# main.net
KiCad netlist of a schematic drawn in Altium Designer
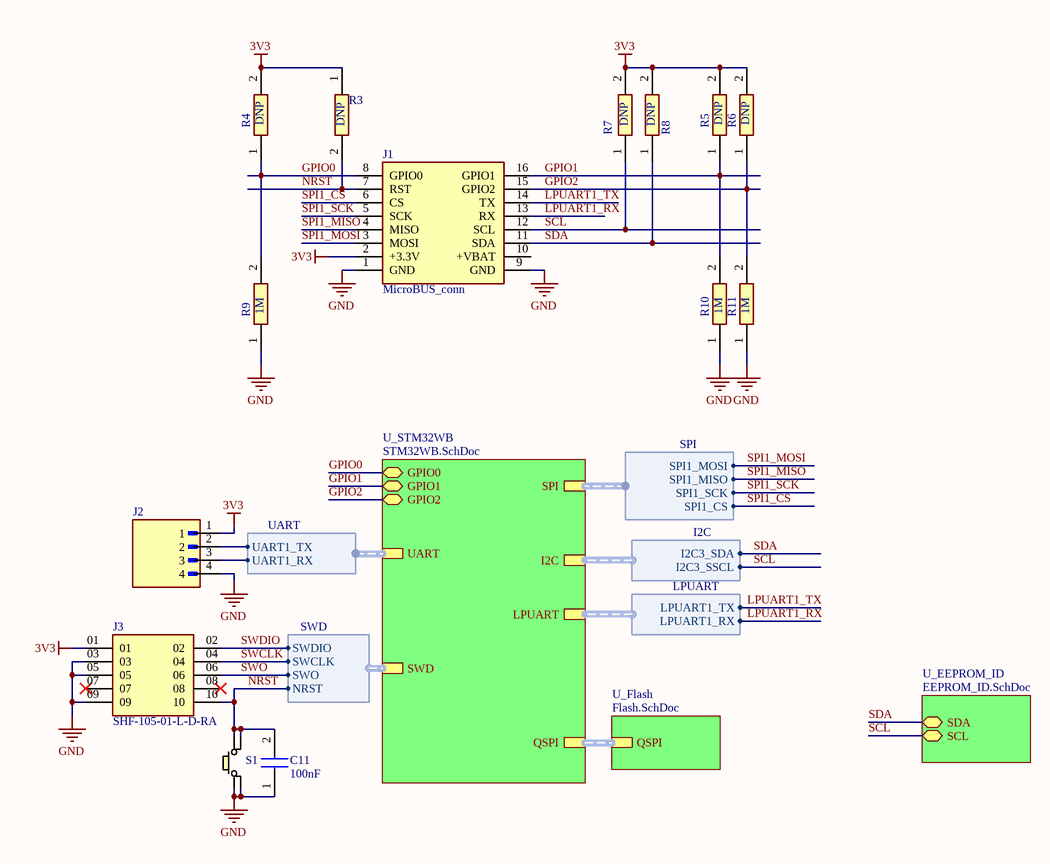
[diagram p0: main.SchDoc]

(export (version "E")
  (design (tool "Eeschema 10.0.6"))
  (components
    (comp (ref "C11")
      (value "100nF")
      (footprint "SamacSys:CAPC1005X70N")
      (description "Capacitor")
      (fields
        (field (name "MANUFACTURER_PART_NUMBER") "GRM155R61A104KA01D")
        (field (name "MOUSER PART NUMBER") "81-GRM155R61A104KA01")
      )
      (libsource (lib "*") (part "GRM155R61A104KA01D"))
    )
    (comp (ref "J1")
      (value "MicroBUS_conn")
      (footprint "SamacSys:MicroBUS_header")
      (description "Connector")
      (fields
        (field (name "MANUFACTURER_PART_NUMBER") "M20-9730845")
        (field (name "MOUSER PART NUMBER") "855-M20-9730845")
      )
      (libsource (lib "SamacSys") (part "MicroBUS_conn"))
    )
    (comp (ref "J2")
      (value "310-87-104-41-205101")
      (footprint "SamacSys:310-87-104-41-205101")
      (libsource (lib "SamacSys") (part "310-87-104-41-205101"))
    )
    (comp (ref "J3")
      (value "SHF-105-01-L-D-RA")
      (footprint "SamacSys:SAMTEC_SHF-105-01-L-D-RA")
      (fields (field (name "MF") "Samtec"))
      (libsource (lib "SamacSys") (part "SHF-105-01-L-D-RA"))
    )
    (comp (ref "R3")
      (value "DNP")
      (footprint "SamacSys:RESC1005X35N")
      (description "Resistor")
      (fields
        (field (name "MANUFACTURER_PART_NUMBER") "RT0402FRE07100KL")
        (field (name "MOUSER PART NUMBER") "603-RT0402FRE07100KL")
      )
      (libsource (lib "*") (part "RT0402FRE07100KL"))
    )
    (comp (ref "R4")
      (value "DNP")
      (footprint "SamacSys:RESC1005X40N")
      (description "Resistor")
      (fields
        (field (name "MANUFACTURER_PART_NUMBER") "RC0402FR-071ML")
        (field (name "MOUSER PART NUMBER") "603-RC0402FR-071ML")
      )
      (libsource (lib "*") (part "RC0402FR-071ML"))
    )
    (comp (ref "R5")
      (value "DNP")
      (footprint "SamacSys:RESC1005X40N")
      (description "Resistor")
      (fields
        (field (name "MANUFACTURER_PART_NUMBER") "RC0402FR-071ML")
        (field (name "MOUSER PART NUMBER") "603-RC0402FR-071ML")
      )
      (libsource (lib "*") (part "RC0402FR-071ML"))
    )
    (comp (ref "R6")
      (value "DNP")
      (footprint "SamacSys:RESC1005X40N")
      (description "Resistor")
      (fields
        (field (name "MANUFACTURER_PART_NUMBER") "RC0402FR-071ML")
        (field (name "MOUSER PART NUMBER") "603-RC0402FR-071ML")
      )
      (libsource (lib "*") (part "RC0402FR-071ML"))
    )
    (comp (ref "R7")
      (value "DNP")
      (footprint "SamacSys:RESC1005X35N")
      (description "Resistor")
      (fields (field (name "MANUFACTURER_PART_NUMBER") "RT0402FRE075K1L"))
      (libsource (lib "SamacSys") (part "RT0402FRE075K1L"))
    )
    (comp (ref "R8")
      (value "DNP")
      (footprint "SamacSys:RESC1005X35N")
      (description "Resistor")
      (fields (field (name "MANUFACTURER_PART_NUMBER") "RT0402FRE075K1L"))
      (libsource (lib "SamacSys") (part "RT0402FRE075K1L"))
    )
    (comp (ref "R9")
      (value "1M")
      (footprint "SamacSys:RESC1005X40N")
      (description "Resistor")
      (fields
        (field (name "MANUFACTURER_PART_NUMBER") "RC0402FR-071ML")
        (field (name "MOUSER PART NUMBER") "603-RC0402FR-071ML")
      )
      (libsource (lib "*") (part "RC0402FR-071ML"))
    )
    (comp (ref "R10")
      (value "1M")
      (footprint "SamacSys:RESC1005X40N")
      (description "Resistor")
      (fields
        (field (name "MANUFACTURER_PART_NUMBER") "RC0402FR-071ML")
        (field (name "MOUSER PART NUMBER") "603-RC0402FR-071ML")
      )
      (libsource (lib "*") (part "RC0402FR-071ML"))
    )
    (comp (ref "R11")
      (value "1M")
      (footprint "SamacSys:RESC1005X40N")
      (description "Resistor")
      (fields
        (field (name "MANUFACTURER_PART_NUMBER") "RC0402FR-071ML")
        (field (name "MOUSER PART NUMBER") "603-RC0402FR-071ML")
      )
      (libsource (lib "*") (part "RC0402FR-071ML"))
    )
    (comp (ref "S1")
      (value "KMR731NG_LFS")
      (footprint "SamacSys:KMR731NGLFS")
      (description "Switch")
      (fields
        (field (name "MANUFACTURER_PART_NUMBER") "KMR731NG LFS")
        (field (name "MOUSER PART NUMBER") "611-KMR731NGLFS")
      )
      (libsource (lib "SamacSys") (part "KMR731NG_LFS"))
    )
  )
  (nets
    (net (code "6") (name "/GPIO0") (class "Default")
      (node (ref "J1") (pin "8") (pinfunction "GPIO0_8") (pintype "passive"))
      (node (ref "R4") (pin "1") (pinfunction "1_1") (pintype "passive"))
      (node (ref "R9") (pin "2") (pinfunction "2_2") (pintype "passive"))
    )
    (net (code "7") (name "/GPIO1") (class "Default")
      (node (ref "J1") (pin "16") (pinfunction "GPIO1_16") (pintype "passive"))
      (node (ref "R10") (pin "2") (pinfunction "2_2") (pintype "passive"))
      (node (ref "R5") (pin "1") (pinfunction "1_1") (pintype "passive"))
    )
    (net (code "8") (name "/GPIO2") (class "Default")
      (node (ref "J1") (pin "15") (pinfunction "GPIO2_15") (pintype "passive"))
      (node (ref "R11") (pin "2") (pinfunction "2_2") (pintype "passive"))
      (node (ref "R6") (pin "1") (pinfunction "1_1") (pintype "passive"))
    )
    (net (code "9") (name "/LPUART1_RX") (class "Default")
      (node (ref "J1") (pin "13") (pinfunction "RX_13") (pintype "passive"))
    )
    (net (code "10") (name "/LPUART1_TX") (class "Default")
      (node (ref "J1") (pin "14") (pinfunction "TX_14") (pintype "passive"))
    )
    (net (code "11") (name "/NRST") (class "Default")
      (node (ref "C11") (pin "2") (pinfunction "2_2") (pintype "passive"))
      (node (ref "J1") (pin "7") (pinfunction "RST_7") (pintype "passive"))
      (node (ref "J3") (pin "10") (pinfunction "10_10") (pintype "passive"))
      (node (ref "R3") (pin "2") (pinfunction "2_2") (pintype "passive"))
      (node (ref "S1") (pin "3") (pinfunction "3_3") (pintype "passive"))
      (node (ref "S1") (pin "4") (pinfunction "4_4") (pintype "passive"))
    )
    (net (code "13") (name "/SCL") (class "Default")
      (node (ref "J1") (pin "12") (pinfunction "SCL_12") (pintype "passive"))
      (node (ref "R7") (pin "1") (pinfunction "1_1") (pintype "passive"))
    )
    (net (code "14") (name "/SDA") (class "Default")
      (node (ref "J1") (pin "11") (pinfunction "SDA_11") (pintype "passive"))
      (node (ref "R8") (pin "1") (pinfunction "1_1") (pintype "passive"))
    )
    (net (code "15") (name "/SPI1_CS") (class "Default")
      (node (ref "J1") (pin "6") (pinfunction "CS_6") (pintype "passive"))
    )
    (net (code "16") (name "/SPI1_MISO") (class "Default")
      (node (ref "J1") (pin "4") (pinfunction "MISO_4") (pintype "passive"))
    )
    (net (code "17") (name "/SPI1_MOSI") (class "Default")
      (node (ref "J1") (pin "3") (pinfunction "MOSI_3") (pintype "passive"))
    )
    (net (code "18") (name "/SPI1_SCK") (class "Default")
      (node (ref "J1") (pin "5") (pinfunction "SCK_5") (pintype "passive"))
    )
    (net (code "19") (name "/SWCLK") (class "Default")
      (node (ref "J3") (pin "04") (pinfunction "04_04") (pintype "passive"))
    )
    (net (code "20") (name "/SWDIO") (class "Default")
      (node (ref "J3") (pin "02") (pinfunction "02_02") (pintype "passive"))
    )
    (net (code "21") (name "/SWO") (class "Default")
      (node (ref "J3") (pin "06") (pinfunction "06_06") (pintype "passive"))
    )
    (net (code "22") (name "/UART1_RX") (class "Default")
      (node (ref "J2") (pin "3") (pinfunction "3_3") (pintype "passive"))
    )
    (net (code "23") (name "/UART1_TX") (class "Default")
      (node (ref "J2") (pin "2") (pinfunction "2_2") (pintype "passive"))
    )
    (net (code "29") (name "3V3") (class "Default")
      (node (ref "J1") (pin "2") (pinfunction "+3.3V_2") (pintype "passive"))
      (node (ref "J2") (pin "1") (pinfunction "1_1") (pintype "passive"))
      (node (ref "J3") (pin "01") (pinfunction "01_01") (pintype "passive"))
      (node (ref "R3") (pin "1") (pinfunction "1_1") (pintype "passive"))
      (node (ref "R4") (pin "2") (pinfunction "2_2") (pintype "passive"))
      (node (ref "R5") (pin "2") (pinfunction "2_2") (pintype "passive"))
      (node (ref "R6") (pin "2") (pinfunction "2_2") (pintype "passive"))
      (node (ref "R7") (pin "2") (pinfunction "2_2") (pintype "passive"))
      (node (ref "R8") (pin "2") (pinfunction "2_2") (pintype "passive"))
    )
    (net (code "30") (name "GND") (class "Default")
      (node (ref "C11") (pin "1") (pinfunction "1_1") (pintype "passive"))
      (node (ref "J1") (pin "1") (pinfunction "GND_1") (pintype "passive"))
      (node (ref "J1") (pin "9") (pinfunction "GND_9") (pintype "passive"))
      (node (ref "J2") (pin "4") (pinfunction "4_4") (pintype "passive"))
      (node (ref "J3") (pin "03") (pinfunction "03_03") (pintype "passive"))
      (node (ref "J3") (pin "05") (pinfunction "05_05") (pintype "passive"))
      (node (ref "J3") (pin "09") (pinfunction "09_09") (pintype "passive"))
      (node (ref "R10") (pin "1") (pinfunction "1_1") (pintype "passive"))
      (node (ref "R11") (pin "1") (pinfunction "1_1") (pintype "passive"))
      (node (ref "R9") (pin "1") (pinfunction "1_1") (pintype "passive"))
      (node (ref "S1") (pin "1") (pinfunction "1_1") (pintype "passive"))
      (node (ref "S1") (pin "2") (pinfunction "2_2") (pintype "passive"))
    )
    (net (code "31") (name "unconnected-(J1-+VBAT-Pad10)") (class "Default")
      (node (ref "J1") (pin "10") (pinfunction "+VBAT_10") (pintype "passive"))
    )
    (net (code "32") (name "unconnected-(J3-Pad07)") (class "Default")
      (node (ref "J3") (pin "07") (pinfunction "07_07") (pintype "passive+no_connect"))
    )
    (net (code "33") (name "unconnected-(J3-Pad08)") (class "Default")
      (node (ref "J3") (pin "08") (pinfunction "08_08") (pintype "passive+no_connect"))
    )
  )
)
